# 12V_For_Bucks.net
KiCad netlist of a schematic drawn in Altium Designer
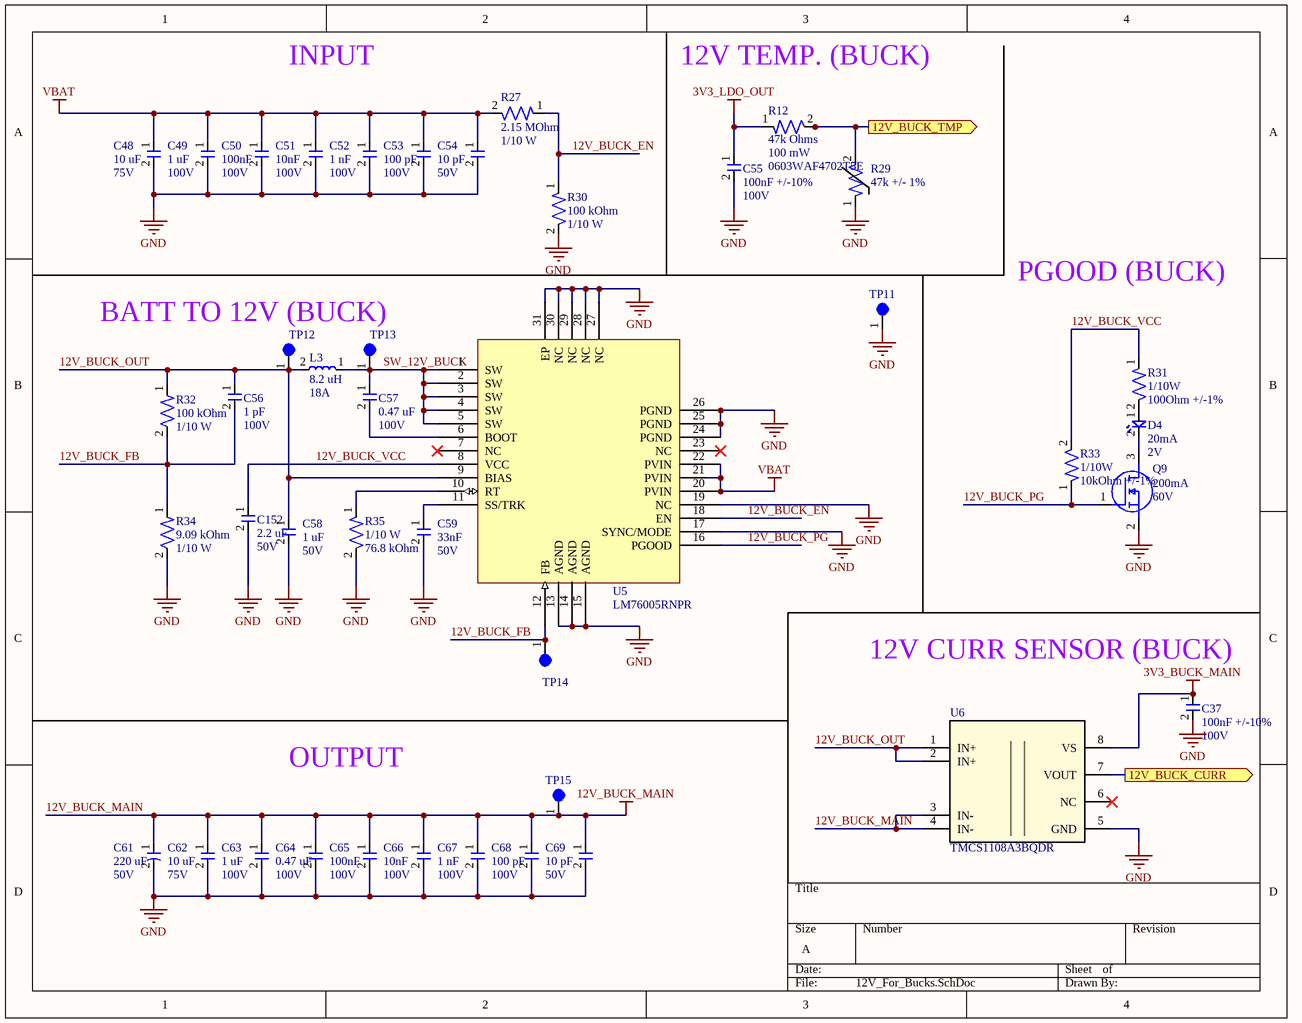
[diagram p0: 12V_For_Bucks.SchDoc]

(export (version "E")
  (design (tool "Eeschema 10.0.6"))
  (components
    (comp (ref "C37")
      (value "CC0603KRX7R0BB104")
      (footprint "CAP-0603")
      (description "CAP CER 0.1UF 100V X7R 0603")
      (fields
        (field (name "MANUFACTURER") "YAGEO")
        (field (name "CAPACITANCE") "100nF +/-10%")
        (field (name "VOLTAGE RATING") "100V")
      )
      (libsource (lib "MasterLib") (part "CAP-100N-0001"))
    )
    (comp (ref "C48")
      (value "C3225X7R1N106K250AC")
      (footprint "CAP-1210")
      (description "10 µF ±10% 75V Ceramic Capacitor X7R 1210 (3225 Metric)")
      (fields (field (name "CAPACITANCE") "10 uF") (field (name "VOLTAGE RATING") "75V"))
      (libsource (lib "MasterLib") (part "CAP-10U-0004"))
    )
    (comp (ref "C49")
      (value "CL31B105KCHNNNE")
      (footprint "CAP-1206 - duplicate")
      (description "1 µF ±10% 100V Ceramic Capacitor X7R 1206 (3216 Metric)")
      (fields (field (name "CAPACITANCE") "1 uF") (field (name "VOLTAGE") "100V"))
      (libsource (lib "MasterLib") (part "CAP-1U-0001"))
    )
    (comp (ref "C50")
      (value "CC0603KRX7R0BB104")
      (footprint "CAP-0603")
      (description "CAP CER 0.1UF 100V X7R 0603")
      (fields
        (field (name "MANUFACTURER") "YAGEO")
        (field (name "CAPACITANCE") "100nF")
        (field (name "VOLTAGE RATING") "100V")
      )
      (libsource (lib "MasterLib") (part "CAP-100N-0001"))
    )
    (comp (ref "C51")
      (value "C1608C0G2A103J080AC")
      (footprint "CAP-0603")
      (description "CAP CER 10000PF 100V C0G 0603")
      (fields
        (field (name "MANUFACTURER") "TDK Corporation")
        (field (name "CAPACITANCE") "10nF")
        (field (name "VOLTAGE RATING") "100V")
      )
      (libsource (lib "MasterLib") (part "CAP-10N-0002"))
    )
    (comp (ref "C52")
      (value "C0603Y102K1RAC7867")
      (footprint "CAP-0603")
      (description "1000 pF ±10% 100V Ceramic Capacitor X7R 0603 (1608 Metric)")
      (fields (field (name "CAPACITANCE") "1 nF") (field (name "VOLTAGE") "100V"))
      (libsource (lib "MasterLib") (part "CAP-1N-0001"))
    )
    (comp (ref "C53")
      (value "0603N101J101CT")
      (footprint "CAP-0603")
      (description "100 pF ±5% 100V Ceramic Capacitor C0G, NP0 0603 (1608 Metric)")
      (fields
        (field (name "TOLERANCE") "+/-5%")
        (field (name "CAPACITANCE") "100 pF")
        (field (name "VOLTAGE") "100V")
      )
      (libsource (lib "MasterLib") (part "CAP-100P-0002"))
    )
    (comp (ref "C54")
      (value "0603N100J500CT")
      (footprint "CAP-0603")
      (description "10 pF ±5% 50V Ceramic Capacitor C0G, NP0 0603 (1608 Metric)")
      (fields
        (field (name "MANUFACTURER") "Walshin Technology Corporation")
        (field (name "CAPACITANCE") "10 pF")
        (field (name "VOLTAGE RATING") "50V")
      )
      (libsource (lib "MasterLib") (part "CAP-10P-0001"))
    )
    (comp (ref "C55")
      (value "CC0603KRX7R0BB104")
      (footprint "CAP-0603")
      (description "CAP CER 0.1UF 100V X7R 0603")
      (fields
        (field (name "MANUFACTURER") "YAGEO")
        (field (name "CAPACITANCE") "100nF +/-10%")
        (field (name "VOLTAGE RATING") "100V")
      )
      (libsource (lib "MasterLib") (part "CAP-100N-0001"))
    )
    (comp (ref "C56")
      (value "885012006087")
      (footprint "CAP-0603")
      (description "1 pF ±0.25pF 100V Ceramic Capacitor C0G, NP0 0603 (1608 Metric)")
      (fields
        (field (name "TOLERANCE") "+/- 0.25 pF")
        (field (name "CAPACITANCE") "1 pF")
        (field (name "VOLTAGE") "100V")
      )
      (libsource (lib "MasterLib") (part "CAP-1P-0001"))
    )
    (comp (ref "C57")
      (value "KAM21KR72A474KL")
      (footprint "CAP-0805")
      (description "0.47 µF ±10% 100V Ceramic Capacitor X7R 0805 (2012 Metric)")
      (fields
        (field (name "TOLERANCE") "+/- 10%")
        (field (name "CAPACITANCE") "0.47 uF")
        (field (name "VOLTAGE") "100V")
      )
      (libsource (lib "MasterLib") (part "CAP-0.47U-0001"))
    )
    (comp (ref "C58")
      (value "UMK107AB7105KA-T")
      (footprint "CAP-0603")
      (description "1 µF ±10% 50V Ceramic Capacitor X7R 0603 (1608 Metric)")
      (fields (field (name "CAPACITANCE") "1 uF") (field (name "VOLTAGE") "50V"))
      (libsource (lib "MasterLib") (part "CAP-1U-0002"))
    )
    (comp (ref "C59")
      (value "CC0603KRX7R9BB333")
      (footprint "CAP-0603")
      (description "0.033 µF ±10% 50V Ceramic Capacitor X7R 0603 (1608 Metric)")
      (fields
        (field (name "MANUFACTURER") "YAGEO")
        (field (name "CAPACITANCE") "33nF")
        (field (name "VOLTAGE RATING") "50V")
      )
      (libsource (lib "MasterLib") (part "CAP-33N-0001"))
    )
    (comp (ref "C61")
      (value "50TZV220M10X10.5")
      (footprint "ELEC-220U-0003")
      (description "220 µF 50 V Aluminum Electrolytic Capacitors Radial, Can - SMD 2000 Hrs @ 105°C")
      (fields (field (name "CAPACITANCE") "220 uF") (field (name "VOLTAGE RATING") "50V"))
      (libsource (lib "MasterLib") (part "ELEC-220U-0003"))
    )
    (comp (ref "C62")
      (value "C3225X7R1N106K250AC")
      (footprint "CAP-1210")
      (description "10 µF ±10% 75V Ceramic Capacitor X7R 1210 (3225 Metric)")
      (fields (field (name "CAPACITANCE") "10 uF") (field (name "VOLTAGE RATING") "75V"))
      (libsource (lib "MasterLib") (part "CAP-10U-0004"))
    )
    (comp (ref "C63")
      (value "CL31B105KCHNNNE")
      (footprint "CAP-1206 - duplicate")
      (description "1 µF ±10% 100V Ceramic Capacitor X7R 1206 (3216 Metric)")
      (fields (field (name "CAPACITANCE") "1 uF") (field (name "VOLTAGE") "100V"))
      (libsource (lib "MasterLib") (part "CAP-1U-0001"))
    )
    (comp (ref "C64")
      (value "KAM21KR72A474KL")
      (footprint "CAP-0805")
      (description "0.47 µF ±10% 100V Ceramic Capacitor X7R 0805 (2012 Metric)")
      (fields
        (field (name "TOLERANCE") "+/- 10%")
        (field (name "CAPACITANCE") "0.47 uF")
        (field (name "VOLTAGE") "100V")
      )
      (libsource (lib "MasterLib") (part "CAP-0.47U-0001"))
    )
    (comp (ref "C65")
      (value "CC0603KRX7R0BB104")
      (footprint "CAP-0603")
      (description "CAP CER 0.1UF 100V X7R 0603")
      (fields
        (field (name "MANUFACTURER") "YAGEO")
        (field (name "CAPACITANCE") "100nF")
        (field (name "VOLTAGE RATING") "100V")
      )
      (libsource (lib "MasterLib") (part "CAP-100N-0001"))
    )
    (comp (ref "C66")
      (value "C1608C0G2A103J080AC")
      (footprint "CAP-0603")
      (description "CAP CER 10000PF 100V C0G 0603")
      (fields
        (field (name "MANUFACTURER") "TDK Corporation")
        (field (name "CAPACITANCE") "10nF")
        (field (name "VOLTAGE RATING") "100V")
      )
      (libsource (lib "MasterLib") (part "CAP-10N-0002"))
    )
    (comp (ref "C67")
      (value "C0603Y102K1RAC7867")
      (footprint "CAP-0603")
      (description "1000 pF ±10% 100V Ceramic Capacitor X7R 0603 (1608 Metric)")
      (fields (field (name "CAPACITANCE") "1 nF") (field (name "VOLTAGE") "100V"))
      (libsource (lib "MasterLib") (part "CAP-1N-0001"))
    )
    (comp (ref "C68")
      (value "0603N101J101CT")
      (footprint "CAP-0603")
      (description "100 pF ±5% 100V Ceramic Capacitor C0G, NP0 0603 (1608 Metric)")
      (fields
        (field (name "TOLERANCE") "+/-5%")
        (field (name "CAPACITANCE") "100 pF")
        (field (name "VOLTAGE") "100V")
      )
      (libsource (lib "MasterLib") (part "CAP-100P-0002"))
    )
    (comp (ref "C69")
      (value "0603N100J500CT")
      (footprint "CAP-0603")
      (description "10 pF ±5% 50V Ceramic Capacitor C0G, NP0 0603 (1608 Metric)")
      (fields
        (field (name "MANUFACTURER") "Walshin Technology Corporation")
        (field (name "CAPACITANCE") "10 pF")
        (field (name "VOLTAGE RATING") "50V")
      )
      (libsource (lib "MasterLib") (part "CAP-10P-0001"))
    )
    (comp (ref "C152")
      (value "UMK107BBJ225KA-T")
      (footprint "CAP-0603")
      (description "2.2 µF ±10% 50V Ceramic Capacitor X5R 0603 (1608 Metric)")
      (fields (field (name "CAPACITANCE") "2.2 uF") (field (name "OLTAGE") "50V"))
      (libsource (lib "MasterLib") (part "CAP-2.2U-0001"))
    )
    (comp (ref "D4")
      (value "150060AS75000")
      (footprint "LED-0603")
      (description "CAP CER 0.1UF 100V X7R 0603")
      (fields
        (field (name "MANUFACTURER") "Wurth Electronik")
        (field (name "CURRENT RATING") "20mA")
        (field (name "VF") "2V")
      )
      (libsource (lib "MasterLib") (part "LED_Amber_0001"))
    )
    (comp (ref "L3")
      (value "IHLP6767GZER8R2M01")
      (footprint "PWRIND-8.2U-0002")
      (description "8.2 µH Shielded Molded Inductor 18 A 10.66mOhm Max Nonstandard")
      (fields
        (field (name "TOLERANCE") "+/-20%")
        (field (name "INDUCTANCE") "8.2 uH")
        (field (name "DCI") "18A")
      )
      (libsource (lib "MasterLib") (part "PWRIND-8.2U-0002"))
    )
    (comp (ref "Q9")
      (value "T2N7002AK,LM")
      (footprint "NMOS-SOT23-3")
      (description "MOSFET N-CH 60V 200MA SOT23")
      (fields
        (field (name "MANUFACTURER") "Toshiba")
        (field (name "ID-CONTINUOUS") "200mA")
        (field (name "VDS-MAX") "60V")
      )
      (libsource (lib "MasterLib") (part "NMOS-200MA-0001"))
    )
    (comp (ref "R12")
      (value "0603WAF4702T5E")
      (footprint "RES-0603")
      (description "100mW Thick Film Resistors 75V ±100ppm/℃ ±1% 47kΩ 0603 Chip Resistor - Surface Mount ROHS")
      (fields (field (name "POWER") "100mW"))
      (libsource (lib "MasterLib") (part "RES-47k-0001-JLC"))
    )
    (comp (ref "R27")
      (value "RC0603FR-072M15L")
      (footprint "RES-0603")
      (description "2.15 MOhms ±1% 0.1W, 1/10W Chip Resistor 0603 (1608 Metric) Moisture Resistant Thick Film")
      (fields
        (field (name "TOLERANCE") "+/-1%")
        (field (name "RESISTANCE") "2.15 MOhm")
        (field (name "POWER") "1/10 W")
      )
      (libsource (lib "MasterLib") (part "RES-2.15M-0001"))
    )
    (comp (ref "R29")
      (value "TMP6431DECR")
      (footprint "RES-0402")
      (description "PTC Thermistor 47 kOhms 0402 (1006 Metric)")
      (fields (field (name "MANUFACTURER") "Texas Instruments") (field (name "RESISTANCE") "47k +/- 1%"))
      (libsource (lib "MasterLib") (part "THERM-47K-0001"))
    )
    (comp (ref "R30")
      (value "RC0603FR-07100KL")
      (footprint "RES-0603")
      (description "100 kOhms ±1% 0.1W, 1/10W Chip Resistor 0603 (1608 Metric) Moisture Resistant Thick Film")
      (fields
        (field (name "TOLERANCE") "+/- 1%")
        (field (name "RESISTANCE") "100 kOhm")
        (field (name "POWER") "1/10 W")
      )
      (libsource (lib "MasterLib") (part "RES-100K-0003"))
    )
    (comp (ref "R31")
      (value "AC0603FR-10100RL")
      (footprint "RES-0603")
      (description "100 Ohms ±1% 0.1W, 1/10W Chip Resistor 0603 (1608 Metric) Automotive AEC-Q200 Thick Film")
      (fields
        (field (name "MANUFACTURER") "YAGEO")
        (field (name "POWER RATING") "1/10W")
        (field (name "RESISTANCE") "100Ohm +/-1%")
      )
      (libsource (lib "MasterLib") (part "RES-100-0002"))
    )
    (comp (ref "R32")
      (value "RC0603FR-07100KL")
      (footprint "RES-0603")
      (description "100 kOhms ±1% 0.1W, 1/10W Chip Resistor 0603 (1608 Metric) Moisture Resistant Thick Film")
      (fields
        (field (name "TOLERANCE") "+/- 1%")
        (field (name "RESISTANCE") "100 kOhm")
        (field (name "POWER") "1/10 W")
      )
      (libsource (lib "MasterLib") (part "RES-100K-0003"))
    )
    (comp (ref "R33")
      (value "RC0603FR-0710KP")
      (footprint "RES-0603")
      (description "RES SMD 10K OHM 1% 1/10W 0603")
      (fields
        (field (name "MANUFACTURER") "YAGEO")
        (field (name "POWER RATING") "1/10W")
        (field (name "RESISTANCE") "10kOhm +/-1%")
      )
      (libsource (lib "MasterLib") (part "RES-10K-0002"))
    )
    (comp (ref "R34")
      (value "RC0603FR-079K09L")
      (footprint "RES-0603")
      (description "9.09 kOhms ±1% 0.1W, 1/10W Chip Resistor 0603 (1608 Metric) Moisture Resistant Thick Film")
      (fields
        (field (name "TOLERANCE") "+/-1%")
        (field (name "RESISTANCE") "9.09 kOhm")
        (field (name "POWER") "1/10 W")
      )
      (libsource (lib "MasterLib") (part "RES-9.09K-0001"))
    )
    (comp (ref "R35")
      (value "RC0603FR-0776K8L")
      (footprint "RES-0603")
      (description "76.8 kOhms ±1% 0.1W, 1/10W Chip Resistor 0603 (1608 Metric) Moisture Resistant Thick Film")
      (fields
        (field (name "MANUFACTURER") "Yageo")
        (field (name "TOLERANCE") "+/- 1%")
        (field (name "POWER") "1/10 W")
        (field (name "RESISTANCE") "76.8 kOhm")
      )
      (libsource (lib "MasterLib") (part "RES-76.8K-0001"))
    )
    (comp (ref "TP11")
      (value "5003")
      (footprint "TEST-POINT-0001")
      (description "Oranange PC Test Point, Miniature Phoisphor Bronze Silver Plating Through Hole Mounting Type")
      (libsource (lib "MasterLib") (part "TEST-POINT-0001"))
    )
    (comp (ref "TP12")
      (value "5003")
      (footprint "TEST-POINT-0001")
      (description "Oranange PC Test Point, Miniature Phoisphor Bronze Silver Plating Through Hole Mounting Type")
      (libsource (lib "MasterLib") (part "TEST-POINT-0001"))
    )
    (comp (ref "TP13")
      (value "5003")
      (footprint "TEST-POINT-0001")
      (description "Oranange PC Test Point, Miniature Phoisphor Bronze Silver Plating Through Hole Mounting Type")
      (libsource (lib "MasterLib") (part "TEST-POINT-0001"))
    )
    (comp (ref "TP14")
      (value "5003")
      (footprint "TEST-POINT-0001")
      (description "Oranange PC Test Point, Miniature Phoisphor Bronze Silver Plating Through Hole Mounting Type")
      (libsource (lib "MasterLib") (part "TEST-POINT-0001"))
    )
    (comp (ref "TP15")
      (value "5003")
      (footprint "TEST-POINT-0001")
      (description "Oranange PC Test Point, Miniature Phoisphor Bronze Silver Plating Through Hole Mounting Type")
      (libsource (lib "MasterLib") (part "TEST-POINT-0001"))
    )
    (comp (ref "U5")
      (value "LM76005RNPR")
      (footprint "IC-30-WQFN(6x4)")
      (description "Buck Switching Regulator IC Positive Adjustable 1V 1 Output 5A 30-WFQFN Exposed Pad")
      (fields (field (name "MANUFACTURER") "Texas Instruments") (field (name "CURRENT") "LM76005RNPR"))
      (libsource (lib "MasterLib") (part "IC-BUCK-0006"))
    )
    (comp (ref "U6")
      (value "TMCS1108A3BQDR")
      (footprint "D0008A-IPC_A")
      (libsource (lib "MasterLib") (part "IC-CURRENT-0005"))
    )
  )
  (nets
    (net (code "1") (name "/12V_BUCK_CURR") (class "Default")
      (node (ref "U6") (pin "7") (pinfunction "VOUT_7") (pintype "passive"))
    )
    (net (code "2") (name "/12V_BUCK_EN") (class "Default")
      (node (ref "R27") (pin "1") (pinfunction "1_1") (pintype "passive"))
      (node (ref "R30") (pin "1") (pinfunction "1_1") (pintype "passive"))
      (node (ref "U5") (pin "18") (pinfunction "EN_18") (pintype "power_in"))
    )
    (net (code "3") (name "/12V_BUCK_FB") (class "Default")
      (node (ref "C56") (pin "2") (pinfunction "2_2") (pintype "passive"))
      (node (ref "R32") (pin "2") (pinfunction "2_2") (pintype "passive"))
      (node (ref "R34") (pin "1") (pinfunction "1_1") (pintype "passive"))
      (node (ref "TP14") (pin "1") (pinfunction "0_1") (pintype "passive"))
      (node (ref "U5") (pin "12") (pinfunction "FB_12") (pintype "input"))
    )
    (net (code "4") (name "/12V_BUCK_OUT") (class "Default")
      (node (ref "C56") (pin "1") (pinfunction "1_1") (pintype "passive"))
      (node (ref "C58") (pin "1") (pinfunction "1_1") (pintype "passive"))
      (node (ref "L3") (pin "2") (pinfunction "2_2") (pintype "passive"))
      (node (ref "R32") (pin "1") (pinfunction "1_1") (pintype "passive"))
      (node (ref "TP12") (pin "1") (pinfunction "0_1") (pintype "passive"))
      (node (ref "U5") (pin "9") (pinfunction "BIAS_9") (pintype "power_in"))
      (node (ref "U6") (pin "1") (pinfunction "IN+_1") (pintype "passive"))
      (node (ref "U6") (pin "2") (pinfunction "IN+_2") (pintype "passive"))
    )
    (net (code "5") (name "/12V_BUCK_PG") (class "Default")
      (node (ref "Q9") (pin "1") (pinfunction "G_1") (pintype "passive"))
      (node (ref "R33") (pin "1") (pinfunction "1_1") (pintype "passive"))
      (node (ref "U5") (pin "16") (pinfunction "PGOOD_16") (pintype "power_in"))
    )
    (net (code "6") (name "/12V_BUCK_TMP") (class "Default")
      (node (ref "R12") (pin "2") (pinfunction "2_2") (pintype "passive"))
      (node (ref "R29") (pin "2") (pinfunction "2_2") (pintype "passive"))
    )
    (net (code "7") (name "/12V_BUCK_VCC") (class "Default")
      (node (ref "C152") (pin "1") (pinfunction "1_1") (pintype "passive"))
      (node (ref "R31") (pin "1") (pinfunction "1_1") (pintype "passive"))
      (node (ref "R33") (pin "2") (pinfunction "2_2") (pintype "passive"))
      (node (ref "U5") (pin "8") (pinfunction "VCC_8") (pintype "power_in"))
    )
    (net (code "8") (name "/SW_12V_BUCK") (class "Default")
      (node (ref "C57") (pin "1") (pinfunction "1_1") (pintype "passive"))
      (node (ref "L3") (pin "1") (pinfunction "1_1") (pintype "passive"))
      (node (ref "TP13") (pin "1") (pinfunction "0_1") (pintype "passive"))
      (node (ref "U5") (pin "1") (pinfunction "SW_1") (pintype "power_in"))
      (node (ref "U5") (pin "2") (pinfunction "SW_2") (pintype "power_in"))
      (node (ref "U5") (pin "3") (pinfunction "SW_3") (pintype "power_in"))
      (node (ref "U5") (pin "4") (pinfunction "SW_4") (pintype "power_in"))
      (node (ref "U5") (pin "5") (pinfunction "SW_5") (pintype "power_in"))
    )
    (net (code "9") (name "3V3_BUCK_MAIN") (class "Default")
      (node (ref "C37") (pin "1") (pinfunction "1_1") (pintype "passive"))
      (node (ref "U6") (pin "8") (pinfunction "VS_8") (pintype "power_in"))
    )
    (net (code "10") (name "3V3_LDO_OUT") (class "Default")
      (node (ref "C55") (pin "1") (pinfunction "1_1") (pintype "passive"))
      (node (ref "R12") (pin "1") (pinfunction "1_1") (pintype "passive"))
    )
    (net (code "11") (name "12V_BUCK_MAIN") (class "Default")
      (node (ref "C61") (pin "1") (pinfunction "1_1") (pintype "passive"))
      (node (ref "C62") (pin "1") (pinfunction "1_1") (pintype "passive"))
      (node (ref "C63") (pin "1") (pinfunction "1_1") (pintype "passive"))
      (node (ref "C64") (pin "1") (pinfunction "1_1") (pintype "passive"))
      (node (ref "C65") (pin "1") (pinfunction "1_1") (pintype "passive"))
      (node (ref "C66") (pin "1") (pinfunction "1_1") (pintype "passive"))
      (node (ref "C67") (pin "1") (pinfunction "1_1") (pintype "passive"))
      (node (ref "C68") (pin "1") (pinfunction "1_1") (pintype "passive"))
      (node (ref "C69") (pin "1") (pinfunction "1_1") (pintype "passive"))
      (node (ref "TP15") (pin "1") (pinfunction "0_1") (pintype "passive"))
      (node (ref "U6") (pin "3") (pinfunction "IN-_3") (pintype "passive"))
      (node (ref "U6") (pin "4") (pinfunction "IN-_4") (pintype "passive"))
    )
    (net (code "12") (name "GND") (class "Default")
      (node (ref "C152") (pin "2") (pinfunction "2_2") (pintype "passive"))
      (node (ref "C37") (pin "2") (pinfunction "2_2") (pintype "passive"))
      (node (ref "C48") (pin "2") (pinfunction "2_2") (pintype "passive"))
      (node (ref "C49") (pin "2") (pinfunction "2_2") (pintype "passive"))
      (node (ref "C50") (pin "2") (pinfunction "2_2") (pintype "passive"))
      (node (ref "C51") (pin "2") (pinfunction "2_2") (pintype "passive"))
      (node (ref "C52") (pin "2") (pinfunction "2_2") (pintype "passive"))
      (node (ref "C53") (pin "2") (pinfunction "2_2") (pintype "passive"))
      (node (ref "C54") (pin "2") (pinfunction "2_2") (pintype "passive"))
      (node (ref "C55") (pin "2") (pinfunction "2_2") (pintype "passive"))
      (node (ref "C58") (pin "2") (pinfunction "2_2") (pintype "passive"))
      (node (ref "C59") (pin "2") (pinfunction "2_2") (pintype "passive"))
      (node (ref "C61") (pin "2") (pinfunction "2_2") (pintype "passive"))
      (node (ref "C62") (pin "2") (pinfunction "2_2") (pintype "passive"))
      (node (ref "C63") (pin "2") (pinfunction "2_2") (pintype "passive"))
      (node (ref "C64") (pin "2") (pinfunction "2_2") (pintype "passive"))
      (node (ref "C65") (pin "2") (pinfunction "2_2") (pintype "passive"))
      (node (ref "C66") (pin "2") (pinfunction "2_2") (pintype "passive"))
      (node (ref "C67") (pin "2") (pinfunction "2_2") (pintype "passive"))
      (node (ref "C68") (pin "2") (pinfunction "2_2") (pintype "passive"))
      (node (ref "C69") (pin "2") (pinfunction "2_2") (pintype "passive"))
      (node (ref "Q9") (pin "2") (pinfunction "S_2") (pintype "passive"))
      (node (ref "R29") (pin "1") (pinfunction "1_1") (pintype "passive"))
      (node (ref "R30") (pin "2") (pinfunction "2_2") (pintype "passive"))
      (node (ref "R34") (pin "2") (pinfunction "2_2") (pintype "passive"))
      (node (ref "R35") (pin "2") (pinfunction "2_2") (pintype "passive"))
      (node (ref "TP11") (pin "1") (pinfunction "0_1") (pintype "passive"))
      (node (ref "U5") (pin "13") (pinfunction "AGND_13") (pintype "power_in"))
      (node (ref "U5") (pin "14") (pinfunction "AGND_14") (pintype "power_in"))
      (node (ref "U5") (pin "15") (pinfunction "AGND_15") (pintype "power_in"))
      (node (ref "U5") (pin "17") (pinfunction "SYNC/MODE_17") (pintype "power_in"))
      (node (ref "U5") (pin "19") (pinfunction "NC_19") (pintype "power_in"))
      (node (ref "U5") (pin "24") (pinfunction "PGND_24") (pintype "power_in"))
      (node (ref "U5") (pin "25") (pinfunction "PGND_25") (pintype "power_in"))
      (node (ref "U5") (pin "26") (pinfunction "PGND_26") (pintype "power_in"))
      (node (ref "U5") (pin "27") (pinfunction "NC_27") (pintype "power_in"))
      (node (ref "U5") (pin "28") (pinfunction "NC_28") (pintype "power_in"))
      (node (ref "U5") (pin "29") (pinfunction "NC_29") (pintype "power_in"))
      (node (ref "U5") (pin "30") (pinfunction "NC_30") (pintype "power_in"))
      (node (ref "U5") (pin "31") (pinfunction "EP_31") (pintype "power_in"))
      (node (ref "U6") (pin "5") (pinfunction "GND_5") (pintype "power_in"))
    )
    (net (code "13") (name "Net-(D4-Pad1)") (class "Default")
      (node (ref "D4") (pin "1") (pinfunction "1_1") (pintype "passive"))
      (node (ref "R31") (pin "2") (pinfunction "2_2") (pintype "passive"))
    )
    (net (code "14") (name "Net-(Q9-D)") (class "Default")
      (node (ref "D4") (pin "2") (pinfunction "2_2") (pintype "passive"))
      (node (ref "Q9") (pin "3") (pinfunction "D_3") (pintype "passive"))
    )
    (net (code "15") (name "Net-(U5-BOOT)") (class "Default")
      (node (ref "C57") (pin "2") (pinfunction "2_2") (pintype "passive"))
      (node (ref "U5") (pin "6") (pinfunction "BOOT_6") (pintype "power_in"))
    )
    (net (code "16") (name "Net-(U5-RT)") (class "Default")
      (node (ref "R35") (pin "1") (pinfunction "1_1") (pintype "passive"))
      (node (ref "U5") (pin "10") (pinfunction "RT_10") (pintype "bidirectional"))
    )
    (net (code "17") (name "Net-(U5-SS{slash}TRK)") (class "Default")
      (node (ref "C59") (pin "1") (pinfunction "1_1") (pintype "passive"))
      (node (ref "U5") (pin "11") (pinfunction "SS/TRK_11") (pintype "passive"))
    )
    (net (code "18") (name "VBAT") (class "Default")
      (node (ref "C48") (pin "1") (pinfunction "1_1") (pintype "passive"))
      (node (ref "C49") (pin "1") (pinfunction "1_1") (pintype "passive"))
      (node (ref "C50") (pin "1") (pinfunction "1_1") (pintype "passive"))
      (node (ref "C51") (pin "1") (pinfunction "1_1") (pintype "passive"))
      (node (ref "C52") (pin "1") (pinfunction "1_1") (pintype "passive"))
      (node (ref "C53") (pin "1") (pinfunction "1_1") (pintype "passive"))
      (node (ref "C54") (pin "1") (pinfunction "1_1") (pintype "passive"))
      (node (ref "R27") (pin "2") (pinfunction "2_2") (pintype "passive"))
      (node (ref "U5") (pin "20") (pinfunction "PVIN_20") (pintype "power_in"))
      (node (ref "U5") (pin "21") (pinfunction "PVIN_21") (pintype "power_in"))
      (node (ref "U5") (pin "22") (pinfunction "PVIN_22") (pintype "power_in"))
    )
    (net (code "19") (name "unconnected-(U5-NC-Pad7)") (class "Default")
      (node (ref "U5") (pin "7") (pinfunction "NC_7") (pintype "power_in+no_connect"))
    )
    (net (code "20") (name "unconnected-(U5-NC-Pad23)") (class "Default")
      (node (ref "U5") (pin "23") (pinfunction "NC_23") (pintype "tri_state+no_connect"))
    )
    (net (code "21") (name "unconnected-(U6-NC-Pad6)") (class "Default")
      (node (ref "U6") (pin "6") (pinfunction "NC_6") (pintype "passive+no_connect"))
    )
  )
)
